# MicroProcessor.net
KiCad netlist of a schematic drawn in EAGLE
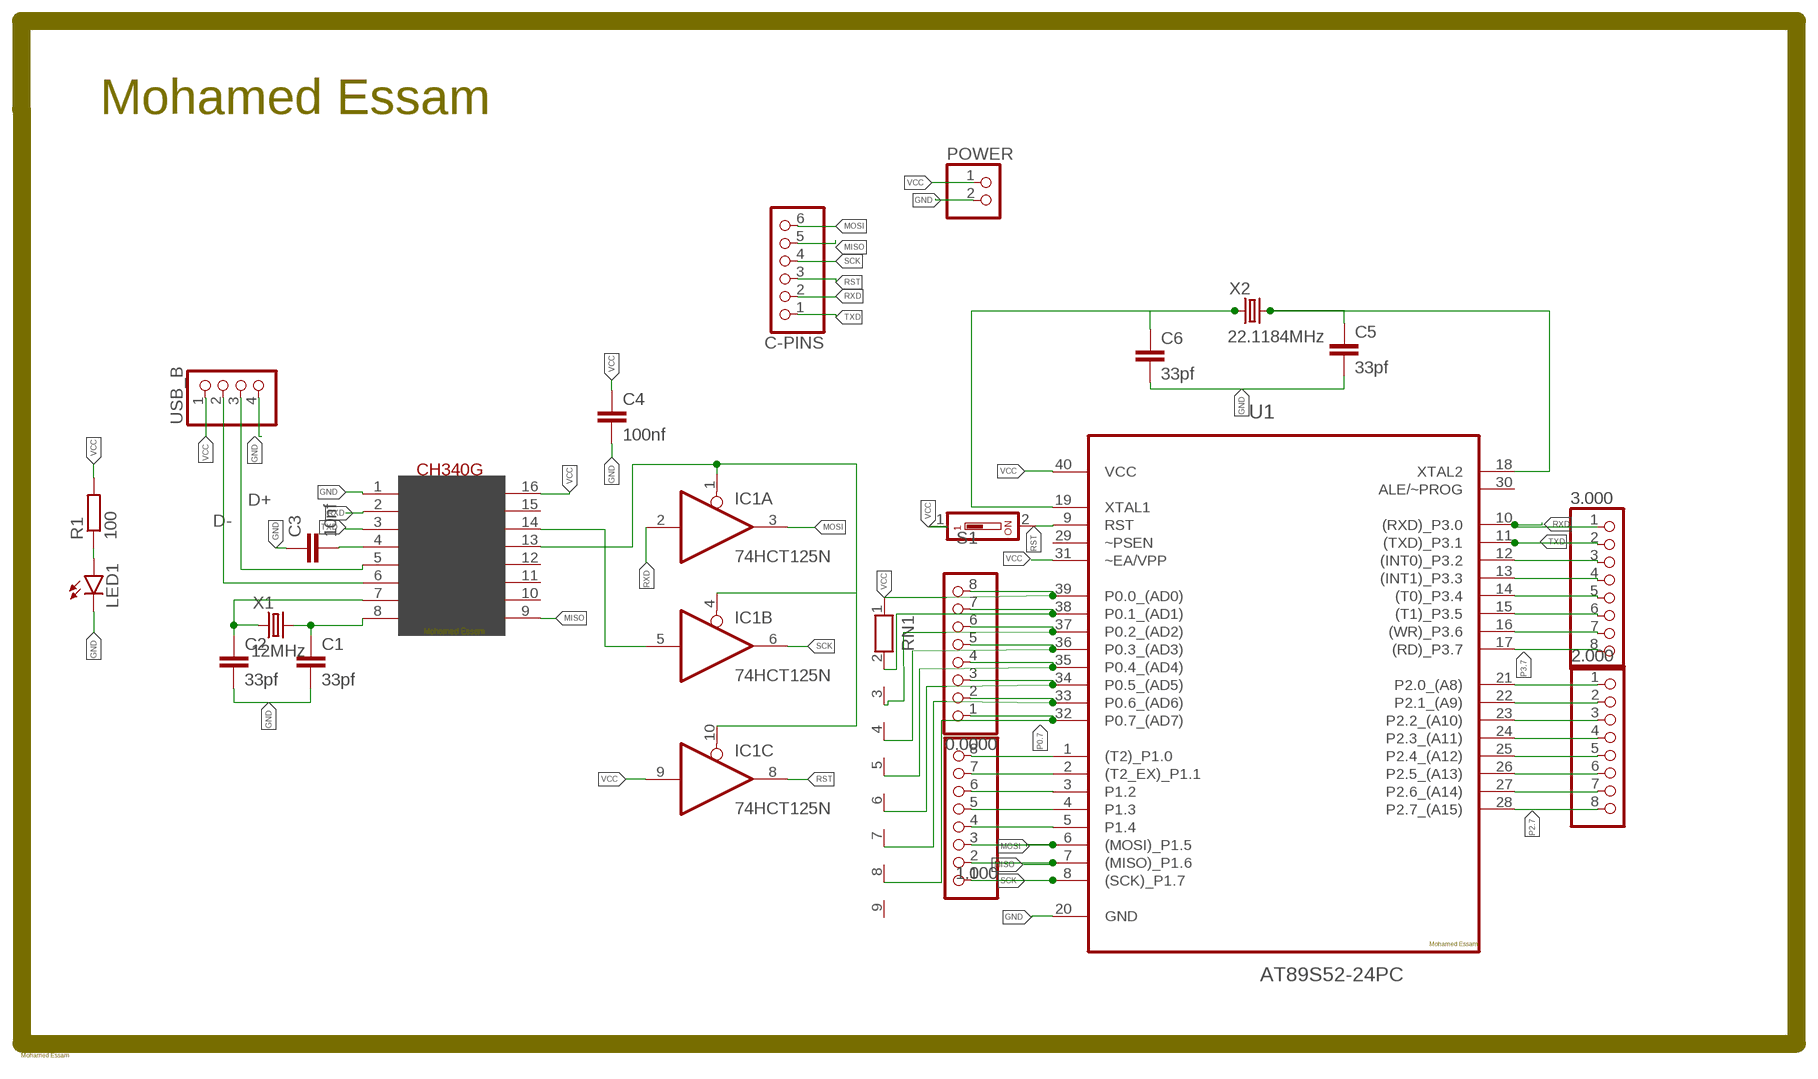
[diagram p0: schematic, sheet 1]

(export (version "E")
  (design (tool "Eeschema 10.0.6"))
  (components
    (comp (ref "0.0000")
      (value "PINHD-1X8")
      (footprint "eagle-import:1X08")
      (libsource (lib "eagle-import") (part "PINHD-1X8"))
    )
    (comp (ref "1.000")
      (value "PINHD-1X8")
      (footprint "eagle-import:1X08")
      (libsource (lib "eagle-import") (part "PINHD-1X8"))
    )
    (comp (ref "2.000")
      (value "PINHD-1X8")
      (footprint "eagle-import:1X08")
      (libsource (lib "eagle-import") (part "PINHD-1X8"))
    )
    (comp (ref "3.000")
      (value "PINHD-1X8")
      (footprint "eagle-import:1X08")
      (libsource (lib "eagle-import") (part "PINHD-1X8"))
    )
    (comp (ref "C-PINS")
      (value "PINHD-1X6")
      (footprint "eagle-import:1X06")
      (libsource (lib "eagle-import") (part "PINHD-1X6"))
    )
    (comp (ref "C1")
      (value "33pf")
      (footprint "eagle-import:C025-025X050")
      (libsource (lib "eagle-import") (part "CAPACITOR"))
    )
    (comp (ref "C2")
      (value "33pf")
      (footprint "eagle-import:C025-025X050")
      (libsource (lib "eagle-import") (part "CAPACITOR"))
    )
    (comp (ref "C3")
      (value "10nf")
      (footprint "eagle-import:C025-025X050")
      (libsource (lib "eagle-import") (part "C-EU025-025X050"))
    )
    (comp (ref "C4")
      (value "100nf")
      (footprint "eagle-import:C025-025X050")
      (libsource (lib "eagle-import") (part "CAPACITOR"))
    )
    (comp (ref "C5")
      (value "33pf")
      (footprint "eagle-import:C025-025X050")
      (libsource (lib "eagle-import") (part "CAPACITOR"))
    )
    (comp (ref "C6")
      (value "33pf")
      (footprint "eagle-import:C025-025X050")
      (libsource (lib "eagle-import") (part "CAPACITOR"))
    )
    (comp (ref "IC1")
      (value "74HCT125N")
      (footprint "eagle-import:DIL14")
      (libsource (lib "eagle-import") (part "74125NHCT"))
    )
    (comp (ref "LED1")
      (value "LED5MM")
      (footprint "eagle-import:LED5MM")
      (libsource (lib "eagle-import") (part "LED5MM"))
    )
    (comp (ref "POWER")
      (value "PINHD-1X2")
      (footprint "eagle-import:1X02")
      (libsource (lib "eagle-import") (part "PINHD-1X2"))
    )
    (comp (ref "R1")
      (value "100")
      (footprint "eagle-import:0204_7")
      (libsource (lib "eagle-import") (part "R-EU_0204/7"))
    )
    (comp (ref "RN1")
      (value "RN08")
      (footprint "eagle-import:RN-9")
      (libsource (lib "eagle-import") (part "RN08"))
    )
    (comp (ref "S1")
      (value "SD4-01")
      (footprint "eagle-import:SD4-01")
      (libsource (lib "eagle-import") (part "SD4-01"))
    )
    (comp (ref "U$1")
      (value "CH340G")
      (footprint "eagle-import:SOIC16")
      (libsource (lib "eagle-import") (part "CH340G"))
    )
    (comp (ref "U1")
      (value "AT89S52-24PC")
      (footprint "eagle-import:DIP254P1524X482-40")
      (fields (field (name "MF") "Microchip"))
      (libsource (lib "eagle-import") (part "AT89S52-24PC"))
    )
    (comp (ref "USB_B")
      (value "PINHD-1X4")
      (footprint "eagle-import:1X04")
      (libsource (lib "eagle-import") (part "PINHD-1X4"))
    )
    (comp (ref "X1")
      (value "12MHz")
      (footprint "eagle-import:XTAL_HC49")
      (fields
        (field (name "MANUFACTURER") "Xinhunjing ")
        (field (name "MPN") "49S/18PF")
        (field (name "CREATED_BY") "PCBLayout.com")
      )
      (libsource (lib "eagle-import") (part "49S/18PF"))
    )
    (comp (ref "X2")
      (value "22.1184MHz")
      (footprint "eagle-import:XTAL_HC49")
      (fields
        (field (name "MANUFACTURER") "Xinhunjing ")
        (field (name "MPN") "49S/18PF")
        (field (name "CREATED_BY") "PCBLayout.com")
      )
      (libsource (lib "eagle-import") (part "49S/18PF"))
    )
  )
  (nets
    (net (code "1") (name "/D+") (class "Default")
      (node (ref "U$1") (pin "5") (pinfunction "D+_5") (pintype "bidirectional"))
      (node (ref "USB_B") (pin "3") (pinfunction "3_3") (pintype "passive"))
    )
    (net (code "2") (name "/D-") (class "Default")
      (node (ref "U$1") (pin "6") (pinfunction "D-_6") (pintype "bidirectional"))
      (node (ref "USB_B") (pin "2") (pinfunction "2_2") (pintype "passive"))
    )
    (net (code "3") (name "GND") (class "Default")
      (node (ref "C1") (pin "2") (pinfunction "2_2") (pintype "passive"))
      (node (ref "C2") (pin "2") (pinfunction "2_2") (pintype "passive"))
      (node (ref "C3") (pin "1") (pinfunction "1_1") (pintype "passive"))
      (node (ref "C4") (pin "2") (pinfunction "2_2") (pintype "passive"))
      (node (ref "C5") (pin "2") (pinfunction "2_2") (pintype "passive"))
      (node (ref "C6") (pin "2") (pinfunction "2_2") (pintype "passive"))
      (node (ref "LED1") (pin "K") (pinfunction "C_K") (pintype "passive"))
      (node (ref "POWER") (pin "2") (pinfunction "2_2") (pintype "passive"))
      (node (ref "U$1") (pin "1") (pinfunction "GND_1") (pintype "bidirectional"))
      (node (ref "U1") (pin "20") (pinfunction "GND_20") (pintype "passive"))
      (node (ref "USB_B") (pin "4") (pinfunction "4_4") (pintype "passive"))
    )
    (net (code "4") (name "MISO") (class "Default")
      (node (ref "1.000") (pin "2") (pinfunction "2_2") (pintype "passive"))
      (node (ref "C-PINS") (pin "5") (pinfunction "5_5") (pintype "passive"))
      (node (ref "U$1") (pin "9") (pinfunction "CTS_9") (pintype "bidirectional"))
      (node (ref "U1") (pin "7") (pinfunction "(MISO)_P1.6_7") (pintype "bidirectional"))
    )
    (net (code "5") (name "MOSI") (class "Default")
      (node (ref "1.000") (pin "3") (pinfunction "3_3") (pintype "passive"))
      (node (ref "C-PINS") (pin "6") (pinfunction "6_6") (pintype "passive"))
      (node (ref "IC1") (pin "3") (pinfunction "O_3") (pintype "tri_state"))
      (node (ref "U1") (pin "6") (pinfunction "(MOSI)_P1.5_6") (pintype "bidirectional"))
    )
    (net (code "6") (name "Net-(IC1A-OE)") (class "Default")
      (node (ref "IC1") (pin "1") (pinfunction "OE_1") (pintype "input"))
      (node (ref "IC1") (pin "10") (pinfunction "OE_10") (pintype "input"))
      (node (ref "IC1") (pin "4") (pinfunction "OE_4") (pintype "input"))
      (node (ref "U$1") (pin "13") (pinfunction "DTR_13") (pintype "bidirectional"))
    )
    (net (code "7") (name "Net-(IC1B-I)") (class "Default")
      (node (ref "IC1") (pin "5") (pinfunction "I_5") (pintype "input"))
      (node (ref "U$1") (pin "14") (pinfunction "RTS_14") (pintype "bidirectional"))
    )
    (net (code "8") (name "Net-(LED1-PadA)") (class "Default")
      (node (ref "LED1") (pin "A") (pinfunction "A_A") (pintype "passive"))
      (node (ref "R1") (pin "1") (pinfunction "1_1") (pintype "passive"))
    )
    (net (code "9") (name "Net-(U$1-V3)") (class "Default")
      (node (ref "C3") (pin "2") (pinfunction "2_2") (pintype "passive"))
      (node (ref "U$1") (pin "4") (pinfunction "V3_4") (pintype "bidirectional"))
    )
    (net (code "10") (name "Net-(U$1-XI)") (class "Default")
      (node (ref "C2") (pin "1") (pinfunction "1_1") (pintype "passive"))
      (node (ref "U$1") (pin "7") (pinfunction "XI_7") (pintype "bidirectional"))
      (node (ref "X1") (pin "1") (pinfunction "1_1") (pintype "passive"))
    )
    (net (code "11") (name "Net-(U$1-XO)") (class "Default")
      (node (ref "C1") (pin "1") (pinfunction "1_1") (pintype "passive"))
      (node (ref "U$1") (pin "8") (pinfunction "XO_8") (pintype "bidirectional"))
      (node (ref "X1") (pin "2") (pinfunction "2_2") (pintype "passive"))
    )
    (net (code "12") (name "Net-(U1-(INT0)_P3.2)") (class "Default")
      (node (ref "3.000") (pin "3") (pinfunction "3_3") (pintype "passive"))
      (node (ref "U1") (pin "12") (pinfunction "(INT0)_P3.2_12") (pintype "bidirectional"))
    )
    (net (code "13") (name "Net-(U1-(INT1)_P3.3)") (class "Default")
      (node (ref "3.000") (pin "4") (pinfunction "4_4") (pintype "passive"))
      (node (ref "U1") (pin "13") (pinfunction "(INT1)_P3.3_13") (pintype "bidirectional"))
    )
    (net (code "14") (name "Net-(U1-(T0)_P3.4)") (class "Default")
      (node (ref "3.000") (pin "5") (pinfunction "5_5") (pintype "passive"))
      (node (ref "U1") (pin "14") (pinfunction "(T0)_P3.4_14") (pintype "bidirectional"))
    )
    (net (code "15") (name "Net-(U1-(T1)_P3.5)") (class "Default")
      (node (ref "3.000") (pin "6") (pinfunction "6_6") (pintype "passive"))
      (node (ref "U1") (pin "15") (pinfunction "(T1)_P3.5_15") (pintype "bidirectional"))
    )
    (net (code "16") (name "Net-(U1-(T2)_P1.0)") (class "Default")
      (node (ref "1.000") (pin "8") (pinfunction "8_8") (pintype "passive"))
      (node (ref "U1") (pin "1") (pinfunction "(T2)_P1.0_1") (pintype "bidirectional"))
    )
    (net (code "17") (name "Net-(U1-(T2_EX)_P1.1)") (class "Default")
      (node (ref "1.000") (pin "7") (pinfunction "7_7") (pintype "passive"))
      (node (ref "U1") (pin "2") (pinfunction "(T2_EX)_P1.1_2") (pintype "bidirectional"))
    )
    (net (code "18") (name "Net-(U1-(WR)_P3.6)") (class "Default")
      (node (ref "3.000") (pin "7") (pinfunction "7_7") (pintype "passive"))
      (node (ref "U1") (pin "16") (pinfunction "(WR)_P3.6_16") (pintype "bidirectional"))
    )
    (net (code "19") (name "Net-(U1-P0.1_(AD1))") (class "Default")
      (node (ref "0.0000") (pin "7") (pinfunction "7_7") (pintype "passive"))
      (node (ref "RN1") (pin "2") (pinfunction "2_2") (pintype "passive"))
      (node (ref "U1") (pin "38") (pinfunction "P0.1_(AD1)_38") (pintype "bidirectional"))
    )
    (net (code "20") (name "Net-(U1-P0.2_(AD2))") (class "Default")
      (node (ref "0.0000") (pin "6") (pinfunction "6_6") (pintype "passive"))
      (node (ref "RN1") (pin "3") (pinfunction "3_3") (pintype "passive"))
      (node (ref "U1") (pin "37") (pinfunction "P0.2_(AD2)_37") (pintype "bidirectional"))
    )
    (net (code "21") (name "Net-(U1-P0.3_(AD3))") (class "Default")
      (node (ref "0.0000") (pin "5") (pinfunction "5_5") (pintype "passive"))
      (node (ref "RN1") (pin "4") (pinfunction "4_4") (pintype "passive"))
      (node (ref "U1") (pin "36") (pinfunction "P0.3_(AD3)_36") (pintype "bidirectional"))
    )
    (net (code "22") (name "Net-(U1-P0.4_(AD4))") (class "Default")
      (node (ref "0.0000") (pin "4") (pinfunction "4_4") (pintype "passive"))
      (node (ref "RN1") (pin "5") (pinfunction "5_5") (pintype "passive"))
      (node (ref "U1") (pin "35") (pinfunction "P0.4_(AD4)_35") (pintype "bidirectional"))
    )
    (net (code "23") (name "Net-(U1-P0.5_(AD5))") (class "Default")
      (node (ref "0.0000") (pin "3") (pinfunction "3_3") (pintype "passive"))
      (node (ref "RN1") (pin "6") (pinfunction "6_6") (pintype "passive"))
      (node (ref "U1") (pin "34") (pinfunction "P0.5_(AD5)_34") (pintype "bidirectional"))
    )
    (net (code "24") (name "Net-(U1-P0.6_(AD6))") (class "Default")
      (node (ref "0.0000") (pin "2") (pinfunction "2_2") (pintype "passive"))
      (node (ref "RN1") (pin "7") (pinfunction "7_7") (pintype "passive"))
      (node (ref "U1") (pin "33") (pinfunction "P0.6_(AD6)_33") (pintype "bidirectional"))
    )
    (net (code "25") (name "Net-(U1-P1.2)") (class "Default")
      (node (ref "1.000") (pin "6") (pinfunction "6_6") (pintype "passive"))
      (node (ref "U1") (pin "3") (pinfunction "P1.2_3") (pintype "bidirectional"))
    )
    (net (code "26") (name "Net-(U1-P1.3)") (class "Default")
      (node (ref "1.000") (pin "5") (pinfunction "5_5") (pintype "passive"))
      (node (ref "U1") (pin "4") (pinfunction "P1.3_4") (pintype "bidirectional"))
    )
    (net (code "27") (name "Net-(U1-P1.4)") (class "Default")
      (node (ref "1.000") (pin "4") (pinfunction "4_4") (pintype "passive"))
      (node (ref "U1") (pin "5") (pinfunction "P1.4_5") (pintype "bidirectional"))
    )
    (net (code "28") (name "Net-(U1-P2.0_(A8))") (class "Default")
      (node (ref "2.000") (pin "1") (pinfunction "1_1") (pintype "passive"))
      (node (ref "U1") (pin "21") (pinfunction "P2.0_(A8)_21") (pintype "bidirectional"))
    )
    (net (code "29") (name "Net-(U1-P2.1_(A9))") (class "Default")
      (node (ref "2.000") (pin "2") (pinfunction "2_2") (pintype "passive"))
      (node (ref "U1") (pin "22") (pinfunction "P2.1_(A9)_22") (pintype "bidirectional"))
    )
    (net (code "30") (name "Net-(U1-P2.2_(A10))") (class "Default")
      (node (ref "2.000") (pin "3") (pinfunction "3_3") (pintype "passive"))
      (node (ref "U1") (pin "23") (pinfunction "P2.2_(A10)_23") (pintype "bidirectional"))
    )
    (net (code "31") (name "Net-(U1-P2.3_(A11))") (class "Default")
      (node (ref "2.000") (pin "4") (pinfunction "4_4") (pintype "passive"))
      (node (ref "U1") (pin "24") (pinfunction "P2.3_(A11)_24") (pintype "bidirectional"))
    )
    (net (code "32") (name "Net-(U1-P2.4_(A12))") (class "Default")
      (node (ref "2.000") (pin "5") (pinfunction "5_5") (pintype "passive"))
      (node (ref "U1") (pin "25") (pinfunction "P2.4_(A12)_25") (pintype "bidirectional"))
    )
    (net (code "33") (name "Net-(U1-P2.5_(A13))") (class "Default")
      (node (ref "2.000") (pin "6") (pinfunction "6_6") (pintype "passive"))
      (node (ref "U1") (pin "26") (pinfunction "P2.5_(A13)_26") (pintype "bidirectional"))
    )
    (net (code "34") (name "Net-(U1-P2.6_(A14))") (class "Default")
      (node (ref "2.000") (pin "7") (pinfunction "7_7") (pintype "passive"))
      (node (ref "U1") (pin "27") (pinfunction "P2.6_(A14)_27") (pintype "bidirectional"))
    )
    (net (code "35") (name "Net-(U1-XTAL1)") (class "Default")
      (node (ref "C6") (pin "1") (pinfunction "1_1") (pintype "passive"))
      (node (ref "U1") (pin "19") (pinfunction "XTAL1_19") (pintype "input"))
      (node (ref "X2") (pin "1") (pinfunction "1_1") (pintype "passive"))
    )
    (net (code "36") (name "Net-(U1-XTAL2)") (class "Default")
      (node (ref "C5") (pin "1") (pinfunction "1_1") (pintype "passive"))
      (node (ref "U1") (pin "18") (pinfunction "XTAL2_18") (pintype "output"))
      (node (ref "X2") (pin "2") (pinfunction "2_2") (pintype "passive"))
    )
    (net (code "37") (name "P0.7") (class "Default")
      (node (ref "0.0000") (pin "1") (pinfunction "1_1") (pintype "passive"))
      (node (ref "RN1") (pin "8") (pinfunction "8_8") (pintype "passive"))
      (node (ref "U1") (pin "32") (pinfunction "P0.7_(AD7)_32") (pintype "bidirectional"))
    )
    (net (code "38") (name "P2.7") (class "Default")
      (node (ref "2.000") (pin "8") (pinfunction "8_8") (pintype "passive"))
      (node (ref "U1") (pin "28") (pinfunction "P2.7_(A15)_28") (pintype "bidirectional"))
    )
    (net (code "39") (name "P3.7") (class "Default")
      (node (ref "3.000") (pin "8") (pinfunction "8_8") (pintype "passive"))
      (node (ref "U1") (pin "17") (pinfunction "(RD)_P3.7_17") (pintype "bidirectional"))
    )
    (net (code "40") (name "RST") (class "Default")
      (node (ref "C-PINS") (pin "3") (pinfunction "3_3") (pintype "passive"))
      (node (ref "IC1") (pin "8") (pinfunction "O_8") (pintype "tri_state"))
      (node (ref "S1") (pin "2") (pinfunction "2_2") (pintype "passive"))
      (node (ref "U1") (pin "9") (pinfunction "RST_9") (pintype "input"))
    )
    (net (code "41") (name "RXD") (class "Default")
      (node (ref "3.000") (pin "1") (pinfunction "1_1") (pintype "passive"))
      (node (ref "C-PINS") (pin "2") (pinfunction "2_2") (pintype "passive"))
      (node (ref "IC1") (pin "2") (pinfunction "I_2") (pintype "input"))
      (node (ref "U$1") (pin "2") (pinfunction "TX_2") (pintype "bidirectional"))
      (node (ref "U1") (pin "10") (pinfunction "(RXD)_P3.0_10") (pintype "bidirectional"))
    )
    (net (code "42") (name "SCK") (class "Default")
      (node (ref "1.000") (pin "1") (pinfunction "1_1") (pintype "passive"))
      (node (ref "C-PINS") (pin "4") (pinfunction "4_4") (pintype "passive"))
      (node (ref "IC1") (pin "6") (pinfunction "O_6") (pintype "tri_state"))
      (node (ref "U1") (pin "8") (pinfunction "(SCK)_P1.7_8") (pintype "bidirectional"))
    )
    (net (code "43") (name "TXD") (class "Default")
      (node (ref "3.000") (pin "2") (pinfunction "2_2") (pintype "passive"))
      (node (ref "C-PINS") (pin "1") (pinfunction "1_1") (pintype "passive"))
      (node (ref "U$1") (pin "3") (pinfunction "RX_3") (pintype "bidirectional"))
      (node (ref "U1") (pin "11") (pinfunction "(TXD)_P3.1_11") (pintype "bidirectional"))
    )
    (net (code "44") (name "VCC") (class "Default")
      (node (ref "0.0000") (pin "8") (pinfunction "8_8") (pintype "passive"))
      (node (ref "C4") (pin "1") (pinfunction "1_1") (pintype "passive"))
      (node (ref "IC1") (pin "9") (pinfunction "I_9") (pintype "input"))
      (node (ref "POWER") (pin "1") (pinfunction "1_1") (pintype "passive"))
      (node (ref "R1") (pin "2") (pinfunction "2_2") (pintype "passive"))
      (node (ref "RN1") (pin "1") (pinfunction "1_1") (pintype "passive"))
      (node (ref "S1") (pin "1") (pinfunction "1_1") (pintype "passive"))
      (node (ref "U$1") (pin "16") (pinfunction "VCC_16") (pintype "bidirectional"))
      (node (ref "U1") (pin "31") (pinfunction "~{EA/VPP}_31") (pintype "input"))
      (node (ref "U1") (pin "39") (pinfunction "P0.0_(AD0)_39") (pintype "bidirectional"))
      (node (ref "U1") (pin "40") (pinfunction "VCC_40") (pintype "power_in"))
      (node (ref "USB_B") (pin "1") (pinfunction "1_1") (pintype "passive"))
    )
    (net (code "45") (name "unconnected-(RN1-Pad9)") (class "Default")
      (node (ref "RN1") (pin "9") (pinfunction "9_9") (pintype "passive"))
    )
    (net (code "46") (name "unconnected-(U$1-DCD-Pad12)") (class "Default")
      (node (ref "U$1") (pin "12") (pinfunction "DCD_12") (pintype "bidirectional"))
    )
    (net (code "47") (name "unconnected-(U$1-DSR-Pad10)") (class "Default")
      (node (ref "U$1") (pin "10") (pinfunction "DSR_10") (pintype "bidirectional"))
    )
    (net (code "48") (name "unconnected-(U$1-RI-Pad11)") (class "Default")
      (node (ref "U$1") (pin "11") (pinfunction "RI_11") (pintype "bidirectional"))
    )
    (net (code "49") (name "unconnected-(U$1-RS232-Pad15)") (class "Default")
      (node (ref "U$1") (pin "15") (pinfunction "RS232_15") (pintype "bidirectional"))
    )
    (net (code "50") (name "unconnected-(U1-ALE{slash}~{PROG}-Pad30)") (class "Default")
      (node (ref "U1") (pin "30") (pinfunction "ALE/~{PROG}_30") (pintype "output"))
    )
    (net (code "51") (name "unconnected-(U1-~{PSEN}-Pad29)") (class "Default")
      (node (ref "U1") (pin "29") (pinfunction "~{PSEN}_29") (pintype "input"))
    )
  )
)
